# base_shield.net
KiCad netlist of a schematic drawn in EAGLE
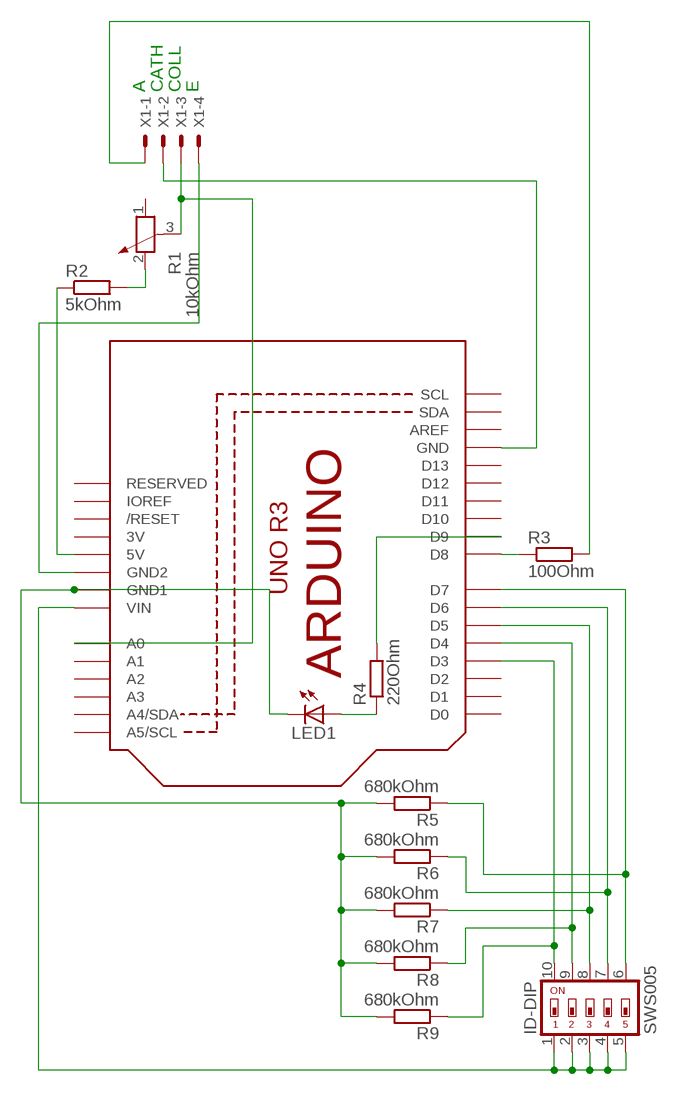
[diagram p0: schematic, sheet 1]

(export (version "E")
  (design (tool "Eeschema 10.0.6"))
  (components
    (comp (ref "ID-DIP")
      (value "SWS005")
      (footprint "eagle-import:SMS-005")
      (libsource (lib "eagle-import") (part "SWS005"))
    )
    (comp (ref "LED1")
      (value "LED3MM")
      (footprint "eagle-import:LED3MM")
      (libsource (lib "eagle-import") (part "LED3MM"))
    )
    (comp (ref "R1")
      (value "10kOhm")
      (footprint "eagle-import:PT-10")
      (libsource (lib "eagle-import") (part "POTENTIOMETER_PT-10"))
    )
    (comp (ref "R2")
      (value "5kOhm")
      (footprint "eagle-import:0204_5")
      (libsource (lib "eagle-import") (part "R-EU_0204/5"))
    )
    (comp (ref "R3")
      (value "100Ohm")
      (footprint "eagle-import:0204_5")
      (libsource (lib "eagle-import") (part "R-EU_0204/5"))
    )
    (comp (ref "R4")
      (value "220Ohm")
      (footprint "eagle-import:0204_5")
      (libsource (lib "eagle-import") (part "R-EU_0204/5"))
    )
    (comp (ref "R5")
      (value "680kOhm")
      (footprint "eagle-import:0204_5")
      (libsource (lib "eagle-import") (part "resistor_348_R-EU_0204/5"))
    )
    (comp (ref "R6")
      (value "680kOhm")
      (footprint "eagle-import:0204_5")
      (libsource (lib "eagle-import") (part "resistor_348_R-EU_0204/5"))
    )
    (comp (ref "R7")
      (value "680kOhm")
      (footprint "eagle-import:0204_5")
      (libsource (lib "eagle-import") (part "resistor_348_R-EU_0204/5"))
    )
    (comp (ref "R8")
      (value "680kOhm")
      (footprint "eagle-import:0204_5")
      (libsource (lib "eagle-import") (part "resistor_348_R-EU_0204/5"))
    )
    (comp (ref "R9")
      (value "680kOhm")
      (footprint "eagle-import:0204_5")
      (libsource (lib "eagle-import") (part "resistor_348_R-EU_0204/5"))
    )
    (comp (ref "U1")
      (value "ARDUINOR3-DIMENSION")
      (footprint "eagle-import:ARDUINOR3")
      (libsource (lib "eagle-import") (part "ARDUINOR3-DIMENSION"))
    )
    (comp (ref "X1")
      (value "KK-156-4")
      (footprint "eagle-import:KK-156-4")
      (fields (field (name "MF") "MOLEX"))
      (libsource (lib "eagle-import") (part "KK-156-4"))
    )
  )
  (nets
    (net (code "1") (name "/3V") (class "Default")
      (node (ref "U1") (pin "3V") (pinfunction "3V_3V") (pintype "power_in"))
    )
    (net (code "2") (name "Net-(ID-DIP-Pad1)") (class "Default")
      (node (ref "ID-DIP") (pin "1") (pinfunction "1_1") (pintype "passive"))
      (node (ref "ID-DIP") (pin "2") (pinfunction "2_2") (pintype "passive"))
      (node (ref "ID-DIP") (pin "3") (pinfunction "3_3") (pintype "passive"))
      (node (ref "ID-DIP") (pin "4") (pinfunction "4_4") (pintype "passive"))
      (node (ref "ID-DIP") (pin "5") (pinfunction "5_5") (pintype "passive"))
      (node (ref "U1") (pin "VIN") (pinfunction "VIN_VIN") (pintype "power_in"))
    )
    (net (code "3") (name "Net-(ID-DIP-Pad6)") (class "Default")
      (node (ref "ID-DIP") (pin "6") (pinfunction "6_6") (pintype "passive"))
      (node (ref "R5") (pin "1") (pinfunction "1_1") (pintype "passive"))
      (node (ref "U1") (pin "D7") (pinfunction "D7_D7") (pintype "bidirectional"))
    )
    (net (code "4") (name "Net-(ID-DIP-Pad7)") (class "Default")
      (node (ref "ID-DIP") (pin "7") (pinfunction "7_7") (pintype "passive"))
      (node (ref "R6") (pin "1") (pinfunction "1_1") (pintype "passive"))
      (node (ref "U1") (pin "D6") (pinfunction "D6_D6") (pintype "bidirectional"))
    )
    (net (code "5") (name "Net-(ID-DIP-Pad8)") (class "Default")
      (node (ref "ID-DIP") (pin "8") (pinfunction "8_8") (pintype "passive"))
      (node (ref "R7") (pin "1") (pinfunction "1_1") (pintype "passive"))
      (node (ref "U1") (pin "D5") (pinfunction "D5_D5") (pintype "bidirectional"))
    )
    (net (code "6") (name "Net-(ID-DIP-Pad9)") (class "Default")
      (node (ref "ID-DIP") (pin "9") (pinfunction "9_9") (pintype "passive"))
      (node (ref "R8") (pin "1") (pinfunction "1_1") (pintype "passive"))
      (node (ref "U1") (pin "D4") (pinfunction "D4_D4") (pintype "bidirectional"))
    )
    (net (code "7") (name "Net-(ID-DIP-Pad10)") (class "Default")
      (node (ref "ID-DIP") (pin "10") (pinfunction "10_10") (pintype "passive"))
      (node (ref "R9") (pin "1") (pinfunction "1_1") (pintype "passive"))
      (node (ref "U1") (pin "D3") (pinfunction "D3_D3") (pintype "bidirectional"))
    )
    (net (code "8") (name "Net-(LED1-C)") (class "Default")
      (node (ref "LED1") (pin "K") (pinfunction "C_K") (pintype "passive"))
      (node (ref "R5") (pin "2") (pinfunction "2_2") (pintype "passive"))
      (node (ref "R6") (pin "2") (pinfunction "2_2") (pintype "passive"))
      (node (ref "R7") (pin "2") (pinfunction "2_2") (pintype "passive"))
      (node (ref "R8") (pin "2") (pinfunction "2_2") (pintype "passive"))
      (node (ref "R9") (pin "2") (pinfunction "2_2") (pintype "passive"))
      (node (ref "U1") (pin "GND1") (pinfunction "GND1_GND1") (pintype "power_in"))
    )
    (net (code "9") (name "Net-(LED1-PadA)") (class "Default")
      (node (ref "LED1") (pin "A") (pinfunction "A_A") (pintype "passive"))
      (node (ref "R4") (pin "1") (pinfunction "1_1") (pintype "passive"))
    )
    (net (code "10") (name "Net-(R1-Pad2)") (class "Default")
      (node (ref "R1") (pin "2") (pinfunction "2_2") (pintype "passive"))
      (node (ref "R2") (pin "2") (pinfunction "2_2") (pintype "passive"))
    )
    (net (code "11") (name "Net-(R2-Pad1)") (class "Default")
      (node (ref "R2") (pin "1") (pinfunction "1_1") (pintype "passive"))
      (node (ref "U1") (pin "5V") (pinfunction "5V_5V") (pintype "power_in"))
    )
    (net (code "12") (name "Net-(R3-Pad1)") (class "Default")
      (node (ref "R3") (pin "1") (pinfunction "1_1") (pintype "passive"))
      (node (ref "U1") (pin "D8") (pinfunction "D8_D8") (pintype "bidirectional"))
    )
    (net (code "13") (name "Net-(R4-Pad2)") (class "Default")
      (node (ref "R4") (pin "2") (pinfunction "2_2") (pintype "passive"))
      (node (ref "U1") (pin "D9") (pinfunction "D9_D9") (pintype "bidirectional"))
    )
    (net (code "14") (name "Net-(X1A-S)") (class "Default")
      (node (ref "R3") (pin "2") (pinfunction "2_2") (pintype "passive"))
      (node (ref "X1") (pin "1") (pinfunction "S_1") (pintype "passive"))
    )
    (net (code "15") (name "Net-(X1B-S)") (class "Default")
      (node (ref "U1") (pin "GND") (pinfunction "GND_GND") (pintype "power_in"))
      (node (ref "X1") (pin "2") (pinfunction "S_2") (pintype "passive"))
    )
    (net (code "16") (name "Net-(X1C-S)") (class "Default")
      (node (ref "R1") (pin "3") (pinfunction "3_3") (pintype "passive"))
      (node (ref "U1") (pin "A0") (pinfunction "A0_A0") (pintype "bidirectional"))
      (node (ref "X1") (pin "3") (pinfunction "S_3") (pintype "passive"))
    )
    (net (code "17") (name "Net-(X1D-S)") (class "Default")
      (node (ref "U1") (pin "GND2") (pinfunction "GND2_GND2") (pintype "power_in"))
      (node (ref "X1") (pin "4") (pinfunction "S_4") (pintype "passive"))
    )
    (net (code "18") (name "unconnected-(R1-Pad1)") (class "Default")
      (node (ref "R1") (pin "1") (pinfunction "1_1") (pintype "passive"))
    )
    (net (code "19") (name "unconnected-(U1-A4{slash}SDA-PadA4)") (class "Default")
      (node (ref "U1") (pin "A4") (pinfunction "A4/SDA_A4") (pintype "bidirectional"))
    )
    (net (code "20") (name "unconnected-(U1-A5{slash}SCL-PadA5)") (class "Default")
      (node (ref "U1") (pin "A5") (pinfunction "A5/SCL_A5") (pintype "bidirectional"))
    )
    (net (code "21") (name "unconnected-(U1-PadA1)") (class "Default")
      (node (ref "U1") (pin "A1") (pinfunction "A1_A1") (pintype "bidirectional"))
    )
    (net (code "22") (name "unconnected-(U1-PadA2)") (class "Default")
      (node (ref "U1") (pin "A2") (pinfunction "A2_A2") (pintype "bidirectional"))
    )
    (net (code "23") (name "unconnected-(U1-PadA3)") (class "Default")
      (node (ref "U1") (pin "A3") (pinfunction "A3_A3") (pintype "bidirectional"))
    )
    (net (code "24") (name "unconnected-(U1-PadAREF)") (class "Default")
      (node (ref "U1") (pin "AREF") (pinfunction "AREF_AREF") (pintype "bidirectional"))
    )
    (net (code "25") (name "unconnected-(U1-PadD0)") (class "Default")
      (node (ref "U1") (pin "D0") (pinfunction "D0_D0") (pintype "bidirectional"))
    )
    (net (code "26") (name "unconnected-(U1-PadD1)") (class "Default")
      (node (ref "U1") (pin "D1") (pinfunction "D1_D1") (pintype "bidirectional"))
    )
    (net (code "27") (name "unconnected-(U1-PadD2)") (class "Default")
      (node (ref "U1") (pin "D2") (pinfunction "D2_D2") (pintype "bidirectional"))
    )
    (net (code "28") (name "unconnected-(U1-PadD10)") (class "Default")
      (node (ref "U1") (pin "D10") (pinfunction "D10_D10") (pintype "bidirectional"))
    )
    (net (code "29") (name "unconnected-(U1-PadD11)") (class "Default")
      (node (ref "U1") (pin "D11") (pinfunction "D11_D11") (pintype "bidirectional"))
    )
    (net (code "30") (name "unconnected-(U1-PadD12)") (class "Default")
      (node (ref "U1") (pin "D12") (pinfunction "D12_D12") (pintype "bidirectional"))
    )
    (net (code "31") (name "unconnected-(U1-PadD13)") (class "Default")
      (node (ref "U1") (pin "D13") (pinfunction "D13_D13") (pintype "bidirectional"))
    )
    (net (code "32") (name "unconnected-(U1-PadIOREF)") (class "Default")
      (node (ref "U1") (pin "IOREF") (pinfunction "IOREF_IOREF") (pintype "output"))
    )
    (net (code "33") (name "unconnected-(U1-PadRESERVED)") (class "Default")
      (node (ref "U1") (pin "RESERVED") (pinfunction "RESERVED_RESERVED") (pintype "no_connect"))
    )
    (net (code "34") (name "unconnected-(U1-PadSCL)") (class "Default")
      (node (ref "U1") (pin "SCL") (pinfunction "SCL_SCL") (pintype "bidirectional"))
    )
    (net (code "35") (name "unconnected-(U1-PadSDA)") (class "Default")
      (node (ref "U1") (pin "SDA") (pinfunction "SDA_SDA") (pintype "bidirectional"))
    )
    (net (code "36") (name "unconnected-(U1-{slash}RESET-PadRESET)") (class "Default")
      (node (ref "U1") (pin "RESET") (pinfunction "/RESET_RESET") (pintype "bidirectional"))
    )
  )
)
